# forcefoot.net
KiCad netlist of a schematic drawn in EAGLE
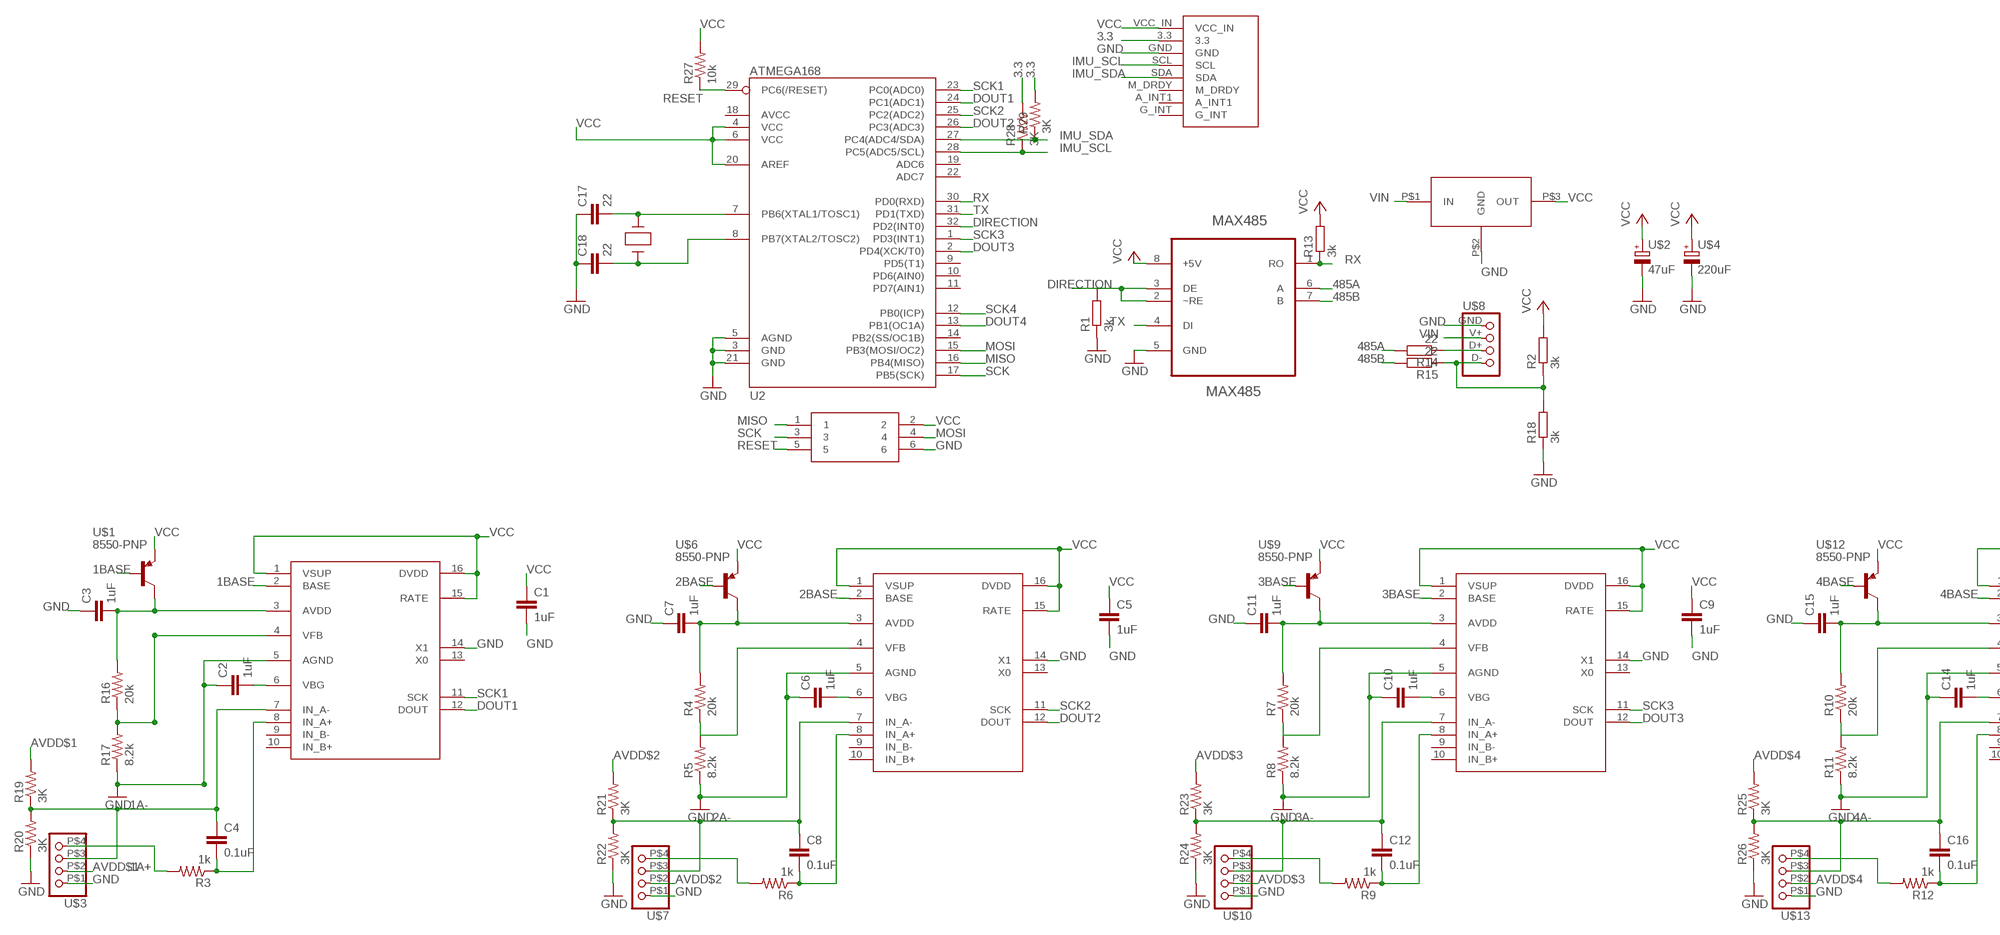
[diagram p0: schematic, sheet 1, part 1 of 2]
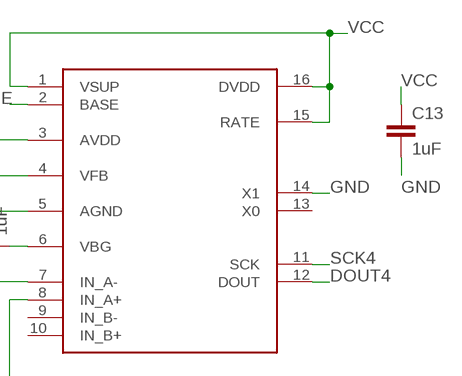
[diagram p1: schematic, sheet 1, part 2 of 2]

(export (version "E")
  (design (tool "Eeschema 10.0.6"))
  (components
    (comp (ref "C1")
      (value "1uF")
      (footprint "eagle-import:0805")
      (libsource (lib "eagle-import") (part "CAP0805"))
    )
    (comp (ref "C2")
      (value "1uF")
      (footprint "eagle-import:0805")
      (libsource (lib "eagle-import") (part "CAP0805"))
    )
    (comp (ref "C3")
      (value "1uF")
      (footprint "eagle-import:0805")
      (libsource (lib "eagle-import") (part "CAP0805"))
    )
    (comp (ref "C4")
      (value "0.1uF")
      (footprint "eagle-import:0805")
      (libsource (lib "eagle-import") (part "CAP0805"))
    )
    (comp (ref "C5")
      (value "1uF")
      (footprint "eagle-import:0805")
      (libsource (lib "eagle-import") (part "CAP0805"))
    )
    (comp (ref "C6")
      (value "1uF")
      (footprint "eagle-import:0805")
      (libsource (lib "eagle-import") (part "CAP0805"))
    )
    (comp (ref "C7")
      (value "1uF")
      (footprint "eagle-import:0805")
      (libsource (lib "eagle-import") (part "CAP0805"))
    )
    (comp (ref "C8")
      (value "0.1uF")
      (footprint "eagle-import:0805")
      (libsource (lib "eagle-import") (part "CAP0805"))
    )
    (comp (ref "C9")
      (value "1uF")
      (footprint "eagle-import:0805")
      (libsource (lib "eagle-import") (part "CAP0805"))
    )
    (comp (ref "C10")
      (value "1uF")
      (footprint "eagle-import:0805")
      (libsource (lib "eagle-import") (part "CAP0805"))
    )
    (comp (ref "C11")
      (value "1uF")
      (footprint "eagle-import:0805")
      (libsource (lib "eagle-import") (part "CAP0805"))
    )
    (comp (ref "C12")
      (value "0.1uF")
      (footprint "eagle-import:0805")
      (libsource (lib "eagle-import") (part "CAP0805"))
    )
    (comp (ref "C13")
      (value "1uF")
      (footprint "eagle-import:0805")
      (libsource (lib "eagle-import") (part "CAP0805"))
    )
    (comp (ref "C14")
      (value "1uF")
      (footprint "eagle-import:0805")
      (libsource (lib "eagle-import") (part "CAP0805"))
    )
    (comp (ref "C15")
      (value "1uF")
      (footprint "eagle-import:0805")
      (libsource (lib "eagle-import") (part "CAP0805"))
    )
    (comp (ref "C16")
      (value "0.1uF")
      (footprint "eagle-import:0805")
      (libsource (lib "eagle-import") (part "CAP0805"))
    )
    (comp (ref "C17")
      (value "22")
      (footprint "eagle-import:C0603")
      (libsource (lib "eagle-import") (part "C_EU_22PF"))
    )
    (comp (ref "C18")
      (value "22")
      (footprint "eagle-import:C0603")
      (libsource (lib "eagle-import") (part "C_EU_22PF"))
    )
    (comp (ref "HX1")
      (value "HX711SO16")
      (footprint "eagle-import:SO16")
      (libsource (lib "eagle-import") (part "HX711SO16"))
    )
    (comp (ref "HX2")
      (value "HX711SO16")
      (footprint "eagle-import:SO16")
      (libsource (lib "eagle-import") (part "HX711SO16"))
    )
    (comp (ref "HX3")
      (value "HX711SO16")
      (footprint "eagle-import:SO16")
      (libsource (lib "eagle-import") (part "HX711SO16"))
    )
    (comp (ref "HX4")
      (value "HX711SO16")
      (footprint "eagle-import:SO16")
      (libsource (lib "eagle-import") (part "HX711SO16"))
    )
    (comp (ref "MAX485")
      (value "MAX485")
      (footprint "eagle-import:SO8")
      (fields (field (name "MPN") "MAX485EESA+"))
      (libsource (lib "eagle-import") (part "MAX485"))
    )
    (comp (ref "R1")
      (value "3k")
      (footprint "eagle-import:R0805")
      (libsource (lib "eagle-import") (part "RESISTANCE-R0805"))
    )
    (comp (ref "R2")
      (value "3k")
      (footprint "eagle-import:R0805")
      (libsource (lib "eagle-import") (part "RESISTANCE-R0805"))
    )
    (comp (ref "R3")
      (value "1k")
      (footprint "eagle-import:0805")
      (libsource (lib "eagle-import") (part "RESISTOR0805-RES"))
    )
    (comp (ref "R4")
      (value "20k")
      (footprint "eagle-import:0805")
      (libsource (lib "eagle-import") (part "RESISTOR0805-RES"))
    )
    (comp (ref "R5")
      (value "8.2k")
      (footprint "eagle-import:0805")
      (libsource (lib "eagle-import") (part "RESISTOR0805-RES"))
    )
    (comp (ref "R6")
      (value "1k")
      (footprint "eagle-import:0805")
      (libsource (lib "eagle-import") (part "RESISTOR0805-RES"))
    )
    (comp (ref "R7")
      (value "20k")
      (footprint "eagle-import:0805")
      (libsource (lib "eagle-import") (part "RESISTOR0805-RES"))
    )
    (comp (ref "R8")
      (value "8.2k")
      (footprint "eagle-import:0805")
      (libsource (lib "eagle-import") (part "RESISTOR0805-RES"))
    )
    (comp (ref "R9")
      (value "1k")
      (footprint "eagle-import:0805")
      (libsource (lib "eagle-import") (part "RESISTOR0805-RES"))
    )
    (comp (ref "R10")
      (value "20k")
      (footprint "eagle-import:0805")
      (libsource (lib "eagle-import") (part "RESISTOR0805-RES"))
    )
    (comp (ref "R11")
      (value "8.2k")
      (footprint "eagle-import:0805")
      (libsource (lib "eagle-import") (part "RESISTOR0805-RES"))
    )
    (comp (ref "R12")
      (value "1k")
      (footprint "eagle-import:0805")
      (libsource (lib "eagle-import") (part "RESISTOR0805-RES"))
    )
    (comp (ref "R13")
      (value "3k")
      (footprint "eagle-import:R0805")
      (libsource (lib "eagle-import") (part "RESISTANCE-R0805"))
    )
    (comp (ref "R14")
      (value "22")
      (footprint "eagle-import:R0805")
      (libsource (lib "eagle-import") (part "RESISTANCE-R0805"))
    )
    (comp (ref "R15")
      (value "22")
      (footprint "eagle-import:R0805")
      (libsource (lib "eagle-import") (part "RESISTANCE-R0805"))
    )
    (comp (ref "R16")
      (value "20k")
      (footprint "eagle-import:0805")
      (libsource (lib "eagle-import") (part "RESISTOR0805-RES"))
    )
    (comp (ref "R17")
      (value "8.2k")
      (footprint "eagle-import:0805")
      (libsource (lib "eagle-import") (part "RESISTOR0805-RES"))
    )
    (comp (ref "R18")
      (value "3k")
      (footprint "eagle-import:R0805")
      (libsource (lib "eagle-import") (part "RESISTANCE-R0805"))
    )
    (comp (ref "R19")
      (value "3K")
      (footprint "eagle-import:0805")
      (libsource (lib "eagle-import") (part "RESISTOR0805-RES"))
    )
    (comp (ref "R20")
      (value "3K")
      (footprint "eagle-import:0805")
      (libsource (lib "eagle-import") (part "RESISTOR0805-RES"))
    )
    (comp (ref "R21")
      (value "3K")
      (footprint "eagle-import:0805")
      (libsource (lib "eagle-import") (part "RESISTOR0805-RES"))
    )
    (comp (ref "R22")
      (value "3K")
      (footprint "eagle-import:0805")
      (libsource (lib "eagle-import") (part "RESISTOR0805-RES"))
    )
    (comp (ref "R23")
      (value "3K")
      (footprint "eagle-import:0805")
      (libsource (lib "eagle-import") (part "RESISTOR0805-RES"))
    )
    (comp (ref "R24")
      (value "3K")
      (footprint "eagle-import:0805")
      (libsource (lib "eagle-import") (part "RESISTOR0805-RES"))
    )
    (comp (ref "R25")
      (value "3K")
      (footprint "eagle-import:0805")
      (libsource (lib "eagle-import") (part "RESISTOR0805-RES"))
    )
    (comp (ref "R26")
      (value "3K")
      (footprint "eagle-import:0805")
      (libsource (lib "eagle-import") (part "RESISTOR0805-RES"))
    )
    (comp (ref "R27")
      (value "10k")
      (footprint "eagle-import:0805")
      (libsource (lib "eagle-import") (part "RESISTOR0805-RES"))
    )
    (comp (ref "R28")
      (value "3K")
      (footprint "eagle-import:0805")
      (libsource (lib "eagle-import") (part "RESISTOR0805-RES"))
    )
    (comp (ref "R29")
      (value "3K")
      (footprint "eagle-import:0805")
      (libsource (lib "eagle-import") (part "RESISTOR0805-RES"))
    )
    (comp (ref "U$1")
      (value "8550-PNP")
      (footprint "eagle-import:SOT-23")
      (libsource (lib "eagle-import") (part "8550-PNP"))
    )
    (comp (ref "U$2")
      (value "47uF")
      (footprint "eagle-import:PANASONIC_D")
      (libsource (lib "eagle-import") (part "CPOL_EUPANASONIC_D"))
    )
    (comp (ref "U$3")
      (value "CONNEC_1X041.5")
      (footprint "eagle-import:4P1.5")
      (libsource (lib "eagle-import") (part "CONNEC_1X041.5"))
    )
    (comp (ref "U$4")
      (value "220uF")
      (footprint "eagle-import:PANASONIC_D8")
      (libsource (lib "eagle-import") (part "CPOL_EUPANASONIC_D8"))
    )
    (comp (ref "U$5")
      (value "REG_5V")
      (footprint "eagle-import:TRACOPOWER")
      (libsource (lib "eagle-import") (part "REG_5V"))
    )
    (comp (ref "U$6")
      (value "8550-PNP")
      (footprint "eagle-import:SOT-23")
      (libsource (lib "eagle-import") (part "8550-PNP"))
    )
    (comp (ref "U$7")
      (value "CONNEC_1X041.5")
      (footprint "eagle-import:4P1.5")
      (libsource (lib "eagle-import") (part "CONNEC_1X041.5"))
    )
    (comp (ref "U$8")
      (value "CONNEC_1X04_485")
      (footprint "eagle-import:CONNEC_485")
      (libsource (lib "eagle-import") (part "CONNEC_1X04_485"))
    )
    (comp (ref "U$9")
      (value "8550-PNP")
      (footprint "eagle-import:SOT-23")
      (libsource (lib "eagle-import") (part "8550-PNP"))
    )
    (comp (ref "U$10")
      (value "CONNEC_1X041.5")
      (footprint "eagle-import:4P1.5")
      (libsource (lib "eagle-import") (part "CONNEC_1X041.5"))
    )
    (comp (ref "U$12")
      (value "8550-PNP")
      (footprint "eagle-import:SOT-23")
      (libsource (lib "eagle-import") (part "8550-PNP"))
    )
    (comp (ref "U$13")
      (value "CONNEC_1X041.5")
      (footprint "eagle-import:4P1.5")
      (libsource (lib "eagle-import") (part "CONNEC_1X041.5"))
    )
    (comp (ref "U$17")
      (value "GY-85")
      (footprint "eagle-import:GY-85")
      (libsource (lib "eagle-import") (part "GY-85"))
    )
    (comp (ref "U$28")
      (value "CONNEC_2X03")
      (footprint "eagle-import:CONNEC_2X03")
      (libsource (lib "eagle-import") (part "CONNEC_2X03"))
    )
    (comp (ref "U2")
      (value "ATMEGA168")
      (footprint "eagle-import:TQFP32-08")
      (libsource (lib "eagle-import") (part "ATMEGA168"))
    )
    (comp (ref "XTAL1")
      (value "QUARTZ")
      (footprint "eagle-import:HC49US")
      (libsource (lib "eagle-import") (part "QUARTZ"))
    )
  )
  (nets
    (net (code "1") (name "/1A+") (class "Default")
      (node (ref "R3") (pin "2") (pinfunction "2_2") (pintype "passive"))
      (node (ref "U$3") (pin "P$4") (pinfunction "4_P$4") (pintype "passive"))
    )
    (net (code "2") (name "/1A-") (class "Default")
      (node (ref "C4") (pin "1") (pinfunction "1_1") (pintype "passive"))
      (node (ref "HX1") (pin "7") (pinfunction "IN_A-_7") (pintype "bidirectional"))
      (node (ref "R19") (pin "1") (pinfunction "1_1") (pintype "passive"))
      (node (ref "R20") (pin "2") (pinfunction "2_2") (pintype "passive"))
      (node (ref "U$3") (pin "P$3") (pinfunction "3_P$3") (pintype "passive"))
    )
    (net (code "3") (name "/1BASE") (class "Default")
      (node (ref "HX1") (pin "2") (pinfunction "BASE_2") (pintype "bidirectional"))
      (node (ref "U$1") (pin "1") (pinfunction "B_1") (pintype "passive"))
    )
    (net (code "4") (name "/2A-") (class "Default")
      (node (ref "C8") (pin "1") (pinfunction "1_1") (pintype "passive"))
      (node (ref "HX2") (pin "7") (pinfunction "IN_A-_7") (pintype "bidirectional"))
      (node (ref "R21") (pin "1") (pinfunction "1_1") (pintype "passive"))
      (node (ref "R22") (pin "2") (pinfunction "2_2") (pintype "passive"))
      (node (ref "U$7") (pin "P$3") (pinfunction "3_P$3") (pintype "passive"))
    )
    (net (code "5") (name "/2BASE") (class "Default")
      (node (ref "HX2") (pin "2") (pinfunction "BASE_2") (pintype "bidirectional"))
      (node (ref "U$6") (pin "1") (pinfunction "B_1") (pintype "passive"))
    )
    (net (code "6") (name "/3.3") (class "Default")
      (node (ref "R28") (pin "2") (pinfunction "2_2") (pintype "passive"))
      (node (ref "R29") (pin "2") (pinfunction "2_2") (pintype "passive"))
      (node (ref "U$17") (pin "3.3") (pinfunction "3.3_3.3") (pintype "bidirectional"))
    )
    (net (code "7") (name "/3A-") (class "Default")
      (node (ref "C12") (pin "1") (pinfunction "1_1") (pintype "passive"))
      (node (ref "HX3") (pin "7") (pinfunction "IN_A-_7") (pintype "bidirectional"))
      (node (ref "R23") (pin "1") (pinfunction "1_1") (pintype "passive"))
      (node (ref "R24") (pin "2") (pinfunction "2_2") (pintype "passive"))
      (node (ref "U$10") (pin "P$3") (pinfunction "3_P$3") (pintype "passive"))
    )
    (net (code "8") (name "/3BASE") (class "Default")
      (node (ref "HX3") (pin "2") (pinfunction "BASE_2") (pintype "bidirectional"))
      (node (ref "U$9") (pin "1") (pinfunction "B_1") (pintype "passive"))
    )
    (net (code "9") (name "/4A-") (class "Default")
      (node (ref "C16") (pin "1") (pinfunction "1_1") (pintype "passive"))
      (node (ref "HX4") (pin "7") (pinfunction "IN_A-_7") (pintype "bidirectional"))
      (node (ref "R25") (pin "1") (pinfunction "1_1") (pintype "passive"))
      (node (ref "R26") (pin "2") (pinfunction "2_2") (pintype "passive"))
      (node (ref "U$13") (pin "P$3") (pinfunction "3_P$3") (pintype "passive"))
    )
    (net (code "10") (name "/4BASE") (class "Default")
      (node (ref "HX4") (pin "2") (pinfunction "BASE_2") (pintype "bidirectional"))
      (node (ref "U$12") (pin "1") (pinfunction "B_1") (pintype "passive"))
    )
    (net (code "11") (name "/485A") (class "Default")
      (node (ref "MAX485") (pin "6") (pinfunction "A_6") (pintype "bidirectional"))
      (node (ref "R14") (pin "2") (pinfunction "2_2") (pintype "passive"))
    )
    (net (code "12") (name "/485B") (class "Default")
      (node (ref "MAX485") (pin "7") (pinfunction "B_7") (pintype "bidirectional"))
      (node (ref "R15") (pin "2") (pinfunction "2_2") (pintype "passive"))
    )
    (net (code "13") (name "/AVDD$1") (class "Default")
      (node (ref "C3") (pin "2") (pinfunction "2_2") (pintype "passive"))
      (node (ref "HX1") (pin "3") (pinfunction "AVDD_3") (pintype "bidirectional"))
      (node (ref "R16") (pin "2") (pinfunction "2_2") (pintype "passive"))
      (node (ref "R19") (pin "2") (pinfunction "2_2") (pintype "passive"))
      (node (ref "U$1") (pin "3") (pinfunction "C_3") (pintype "passive"))
      (node (ref "U$3") (pin "P$2") (pinfunction "2_P$2") (pintype "passive"))
    )
    (net (code "14") (name "/AVDD$2") (class "Default")
      (node (ref "C7") (pin "2") (pinfunction "2_2") (pintype "passive"))
      (node (ref "HX2") (pin "3") (pinfunction "AVDD_3") (pintype "bidirectional"))
      (node (ref "R21") (pin "2") (pinfunction "2_2") (pintype "passive"))
      (node (ref "R4") (pin "2") (pinfunction "2_2") (pintype "passive"))
      (node (ref "U$6") (pin "3") (pinfunction "C_3") (pintype "passive"))
      (node (ref "U$7") (pin "P$2") (pinfunction "2_P$2") (pintype "passive"))
    )
    (net (code "15") (name "/AVDD$3") (class "Default")
      (node (ref "C11") (pin "2") (pinfunction "2_2") (pintype "passive"))
      (node (ref "HX3") (pin "3") (pinfunction "AVDD_3") (pintype "bidirectional"))
      (node (ref "R23") (pin "2") (pinfunction "2_2") (pintype "passive"))
      (node (ref "R7") (pin "2") (pinfunction "2_2") (pintype "passive"))
      (node (ref "U$10") (pin "P$2") (pinfunction "2_P$2") (pintype "passive"))
      (node (ref "U$9") (pin "3") (pinfunction "C_3") (pintype "passive"))
    )
    (net (code "16") (name "/AVDD$4") (class "Default")
      (node (ref "C15") (pin "2") (pinfunction "2_2") (pintype "passive"))
      (node (ref "HX4") (pin "3") (pinfunction "AVDD_3") (pintype "bidirectional"))
      (node (ref "R10") (pin "2") (pinfunction "2_2") (pintype "passive"))
      (node (ref "R25") (pin "2") (pinfunction "2_2") (pintype "passive"))
      (node (ref "U$12") (pin "3") (pinfunction "C_3") (pintype "passive"))
      (node (ref "U$13") (pin "P$2") (pinfunction "2_P$2") (pintype "passive"))
    )
    (net (code "17") (name "/DIRECTION") (class "Default")
      (node (ref "MAX485") (pin "2") (pinfunction "~{RE}_2") (pintype "input"))
      (node (ref "MAX485") (pin "3") (pinfunction "DE_3") (pintype "input"))
      (node (ref "R1") (pin "2") (pinfunction "2_2") (pintype "passive"))
      (node (ref "U2") (pin "32") (pinfunction "PD2(INT0)_32") (pintype "bidirectional"))
    )
    (net (code "18") (name "/DOUT1") (class "Default")
      (node (ref "HX1") (pin "12") (pinfunction "DOUT_12") (pintype "bidirectional"))
      (node (ref "U2") (pin "24") (pinfunction "PC1(ADC1)_24") (pintype "bidirectional"))
    )
    (net (code "19") (name "/DOUT2") (class "Default")
      (node (ref "HX2") (pin "12") (pinfunction "DOUT_12") (pintype "bidirectional"))
      (node (ref "U2") (pin "26") (pinfunction "PC3(ADC3)_26") (pintype "bidirectional"))
    )
    (net (code "20") (name "/DOUT3") (class "Default")
      (node (ref "HX3") (pin "12") (pinfunction "DOUT_12") (pintype "bidirectional"))
      (node (ref "U2") (pin "2") (pinfunction "PD4(XCK/T0)_2") (pintype "bidirectional"))
    )
    (net (code "21") (name "/DOUT4") (class "Default")
      (node (ref "HX4") (pin "12") (pinfunction "DOUT_12") (pintype "bidirectional"))
      (node (ref "U2") (pin "13") (pinfunction "PB1(OC1A)_13") (pintype "bidirectional"))
    )
    (net (code "22") (name "/IMU_SCL") (class "Default")
      (node (ref "R28") (pin "1") (pinfunction "1_1") (pintype "passive"))
      (node (ref "U$17") (pin "SCL") (pinfunction "SCL_SCL") (pintype "bidirectional"))
      (node (ref "U2") (pin "28") (pinfunction "PC5(ADC5/SCL)_28") (pintype "bidirectional"))
    )
    (net (code "23") (name "/IMU_SDA") (class "Default")
      (node (ref "R29") (pin "1") (pinfunction "1_1") (pintype "passive"))
      (node (ref "U$17") (pin "SDA") (pinfunction "SDA_SDA") (pintype "bidirectional"))
      (node (ref "U2") (pin "27") (pinfunction "PC4(ADC4/SDA)_27") (pintype "bidirectional"))
    )
    (net (code "24") (name "/MISO") (class "Default")
      (node (ref "U$28") (pin "1") (pinfunction "1_1") (pintype "bidirectional"))
      (node (ref "U2") (pin "16") (pinfunction "PB4(MISO)_16") (pintype "bidirectional"))
    )
    (net (code "25") (name "/MOSI") (class "Default")
      (node (ref "U$28") (pin "4") (pinfunction "4_4") (pintype "bidirectional"))
      (node (ref "U2") (pin "15") (pinfunction "PB3(MOSI/OC2)_15") (pintype "bidirectional"))
    )
    (net (code "26") (name "/RESET") (class "Default")
      (node (ref "R27") (pin "1") (pinfunction "1_1") (pintype "passive"))
      (node (ref "U$28") (pin "5") (pinfunction "5_5") (pintype "bidirectional"))
      (node (ref "U2") (pin "29") (pinfunction "PC6(/RESET)_29") (pintype "bidirectional"))
    )
    (net (code "27") (name "/RX") (class "Default")
      (node (ref "MAX485") (pin "1") (pinfunction "RO_1") (pintype "output"))
      (node (ref "R13") (pin "1") (pinfunction "1_1") (pintype "passive"))
      (node (ref "U2") (pin "30") (pinfunction "PD0(RXD)_30") (pintype "bidirectional"))
    )
    (net (code "28") (name "/SCK") (class "Default")
      (node (ref "U$28") (pin "3") (pinfunction "3_3") (pintype "bidirectional"))
      (node (ref "U2") (pin "17") (pinfunction "PB5(SCK)_17") (pintype "bidirectional"))
    )
    (net (code "29") (name "/SCK1") (class "Default")
      (node (ref "HX1") (pin "11") (pinfunction "SCK_11") (pintype "bidirectional"))
      (node (ref "U2") (pin "23") (pinfunction "PC0(ADC0)_23") (pintype "bidirectional"))
    )
    (net (code "30") (name "/SCK2") (class "Default")
      (node (ref "HX2") (pin "11") (pinfunction "SCK_11") (pintype "bidirectional"))
      (node (ref "U2") (pin "25") (pinfunction "PC2(ADC2)_25") (pintype "bidirectional"))
    )
    (net (code "31") (name "/SCK3") (class "Default")
      (node (ref "HX3") (pin "11") (pinfunction "SCK_11") (pintype "bidirectional"))
      (node (ref "U2") (pin "1") (pinfunction "PD3(INT1)_1") (pintype "bidirectional"))
    )
    (net (code "32") (name "/SCK4") (class "Default")
      (node (ref "HX4") (pin "11") (pinfunction "SCK_11") (pintype "bidirectional"))
      (node (ref "U2") (pin "12") (pinfunction "PB0(ICP)_12") (pintype "bidirectional"))
    )
    (net (code "33") (name "/TX") (class "Default")
      (node (ref "MAX485") (pin "4") (pinfunction "DI_4") (pintype "input"))
      (node (ref "U2") (pin "31") (pinfunction "PD1(TXD)_31") (pintype "bidirectional"))
    )
    (net (code "34") (name "/VIN") (class "Default")
      (node (ref "U$5") (pin "P$1") (pinfunction "IN_P$1") (pintype "bidirectional"))
      (node (ref "U$8") (pin "V+") (pinfunction "2_V+") (pintype "passive"))
    )
    (net (code "35") (name "GND") (class "Default")
      (node (ref "C1") (pin "2") (pinfunction "2_2") (pintype "passive"))
      (node (ref "C10") (pin "1") (pinfunction "1_1") (pintype "passive"))
      (node (ref "C11") (pin "1") (pinfunction "1_1") (pintype "passive"))
      (node (ref "C13") (pin "2") (pinfunction "2_2") (pintype "passive"))
      (node (ref "C14") (pin "1") (pinfunction "1_1") (pintype "passive"))
      (node (ref "C15") (pin "1") (pinfunction "1_1") (pintype "passive"))
      (node (ref "C17") (pin "1") (pinfunction "1_1") (pintype "passive"))
      (node (ref "C18") (pin "1") (pinfunction "1_1") (pintype "passive"))
      (node (ref "C2") (pin "1") (pinfunction "1_1") (pintype "passive"))
      (node (ref "C3") (pin "1") (pinfunction "1_1") (pintype "passive"))
      (node (ref "C5") (pin "2") (pinfunction "2_2") (pintype "passive"))
      (node (ref "C6") (pin "1") (pinfunction "1_1") (pintype "passive"))
      (node (ref "C7") (pin "1") (pinfunction "1_1") (pintype "passive"))
      (node (ref "C9") (pin "2") (pinfunction "2_2") (pintype "passive"))
      (node (ref "HX1") (pin "14") (pinfunction "X1_14") (pintype "bidirectional"))
      (node (ref "HX1") (pin "5") (pinfunction "AGND_5") (pintype "bidirectional"))
      (node (ref "HX2") (pin "14") (pinfunction "X1_14") (pintype "bidirectional"))
      (node (ref "HX2") (pin "5") (pinfunction "AGND_5") (pintype "bidirectional"))
      (node (ref "HX3") (pin "14") (pinfunction "X1_14") (pintype "bidirectional"))
      (node (ref "HX3") (pin "5") (pinfunction "AGND_5") (pintype "bidirectional"))
      (node (ref "HX4") (pin "14") (pinfunction "X1_14") (pintype "bidirectional"))
      (node (ref "HX4") (pin "5") (pinfunction "AGND_5") (pintype "bidirectional"))
      (node (ref "MAX485") (pin "5") (pinfunction "GND_5") (pintype "passive"))
      (node (ref "R1") (pin "1") (pinfunction "1_1") (pintype "passive"))
      (node (ref "R11") (pin "1") (pinfunction "1_1") (pintype "passive"))
      (node (ref "R17") (pin "1") (pinfunction "1_1") (pintype "passive"))
      (node (ref "R18") (pin "1") (pinfunction "1_1") (pintype "passive"))
      (node (ref "R20") (pin "1") (pinfunction "1_1") (pintype "passive"))
      (node (ref "R22") (pin "1") (pinfunction "1_1") (pintype "passive"))
      (node (ref "R24") (pin "1") (pinfunction "1_1") (pintype "passive"))
      (node (ref "R26") (pin "1") (pinfunction "1_1") (pintype "passive"))
      (node (ref "R5") (pin "1") (pinfunction "1_1") (pintype "passive"))
      (node (ref "R8") (pin "1") (pinfunction "1_1") (pintype "passive"))
      (node (ref "U$10") (pin "P$1") (pinfunction "1_P$1") (pintype "passive"))
      (node (ref "U$13") (pin "P$1") (pinfunction "1_P$1") (pintype "passive"))
      (node (ref "U$17") (pin "GND") (pinfunction "GND_GND") (pintype "bidirectional"))
      (node (ref "U$2") (pin "-") (pinfunction "-_-") (pintype "passive"))
      (node (ref "U$28") (pin "6") (pinfunction "6_6") (pintype "bidirectional"))
      (node (ref "U$3") (pin "P$1") (pinfunction "1_P$1") (pintype "passive"))
      (node (ref "U$4") (pin "-") (pinfunction "-_-") (pintype "passive"))
      (node (ref "U$5") (pin "P$2") (pinfunction "GND_P$2") (pintype "bidirectional"))
      (node (ref "U$7") (pin "P$1") (pinfunction "1_P$1") (pintype "passive"))
      (node (ref "U$8") (pin "GND") (pinfunction "1_GND") (pintype "passive"))
      (node (ref "U2") (pin "21") (pinfunction "GND_21") (pintype "bidirectional"))
      (node (ref "U2") (pin "3") (pinfunction "GND_3") (pintype "bidirectional"))
      (node (ref "U2") (pin "5") (pinfunction "AGND_5") (pintype "bidirectional"))
    )
    (net (code "36") (name "Net-(HX1-IN_A+)") (class "Default")
      (node (ref "C4") (pin "2") (pinfunction "2_2") (pintype "passive"))
      (node (ref "HX1") (pin "8") (pinfunction "IN_A+_8") (pintype "bidirectional"))
      (node (ref "R3") (pin "1") (pinfunction "1_1") (pintype "passive"))
    )
    (net (code "37") (name "Net-(HX1-VBG)") (class "Default")
      (node (ref "C2") (pin "2") (pinfunction "2_2") (pintype "passive"))
      (node (ref "HX1") (pin "6") (pinfunction "VBG_6") (pintype "bidirectional"))
    )
    (net (code "38") (name "Net-(HX1-VFB)") (class "Default")
      (node (ref "HX1") (pin "4") (pinfunction "VFB_4") (pintype "bidirectional"))
      (node (ref "R16") (pin "1") (pinfunction "1_1") (pintype "passive"))
      (node (ref "R17") (pin "2") (pinfunction "2_2") (pintype "passive"))
    )
    (net (code "39") (name "Net-(HX2-IN_A+)") (class "Default")
      (node (ref "C8") (pin "2") (pinfunction "2_2") (pintype "passive"))
      (node (ref "HX2") (pin "8") (pinfunction "IN_A+_8") (pintype "bidirectional"))
      (node (ref "R6") (pin "1") (pinfunction "1_1") (pintype "passive"))
    )
    (net (code "40") (name "Net-(HX2-VBG)") (class "Default")
      (node (ref "C6") (pin "2") (pinfunction "2_2") (pintype "passive"))
      (node (ref "HX2") (pin "6") (pinfunction "VBG_6") (pintype "bidirectional"))
    )
    (net (code "41") (name "Net-(HX2-VFB)") (class "Default")
      (node (ref "HX2") (pin "4") (pinfunction "VFB_4") (pintype "bidirectional"))
      (node (ref "R4") (pin "1") (pinfunction "1_1") (pintype "passive"))
      (node (ref "R5") (pin "2") (pinfunction "2_2") (pintype "passive"))
    )
    (net (code "42") (name "Net-(HX3-IN_A+)") (class "Default")
      (node (ref "C12") (pin "2") (pinfunction "2_2") (pintype "passive"))
      (node (ref "HX3") (pin "8") (pinfunction "IN_A+_8") (pintype "bidirectional"))
      (node (ref "R9") (pin "1") (pinfunction "1_1") (pintype "passive"))
    )
    (net (code "43") (name "Net-(HX3-VBG)") (class "Default")
      (node (ref "C10") (pin "2") (pinfunction "2_2") (pintype "passive"))
      (node (ref "HX3") (pin "6") (pinfunction "VBG_6") (pintype "bidirectional"))
    )
    (net (code "44") (name "Net-(HX3-VFB)") (class "Default")
      (node (ref "HX3") (pin "4") (pinfunction "VFB_4") (pintype "bidirectional"))
      (node (ref "R7") (pin "1") (pinfunction "1_1") (pintype "passive"))
      (node (ref "R8") (pin "2") (pinfunction "2_2") (pintype "passive"))
    )
    (net (code "45") (name "Net-(HX4-IN_A+)") (class "Default")
      (node (ref "C16") (pin "2") (pinfunction "2_2") (pintype "passive"))
      (node (ref "HX4") (pin "8") (pinfunction "IN_A+_8") (pintype "bidirectional"))
      (node (ref "R12") (pin "1") (pinfunction "1_1") (pintype "passive"))
    )
    (net (code "46") (name "Net-(HX4-VBG)") (class "Default")
      (node (ref "C14") (pin "2") (pinfunction "2_2") (pintype "passive"))
      (node (ref "HX4") (pin "6") (pinfunction "VBG_6") (pintype "bidirectional"))
    )
    (net (code "47") (name "Net-(HX4-VFB)") (class "Default")
      (node (ref "HX4") (pin "4") (pinfunction "VFB_4") (pintype "bidirectional"))
      (node (ref "R10") (pin "1") (pinfunction "1_1") (pintype "passive"))
      (node (ref "R11") (pin "2") (pinfunction "2_2") (pintype "passive"))
    )
    (net (code "48") (name "Net-(U$7-4)") (class "Default")
      (node (ref "R6") (pin "2") (pinfunction "2_2") (pintype "passive"))
      (node (ref "U$7") (pin "P$4") (pinfunction "4_P$4") (pintype "passive"))
    )
    (net (code "49") (name "Net-(U$8-3)") (class "Default")
      (node (ref "R14") (pin "1") (pinfunction "1_1") (pintype "passive"))
      (node (ref "U$8") (pin "D+") (pinfunction "3_D+") (pintype "passive"))
    )
    (net (code "50") (name "Net-(U$8-4)") (class "Default")
      (node (ref "R15") (pin "1") (pinfunction "1_1") (pintype "passive"))
      (node (ref "R18") (pin "2") (pinfunction "2_2") (pintype "passive"))
      (node (ref "R2") (pin "1") (pinfunction "1_1") (pintype "passive"))
      (node (ref "U$8") (pin "D-") (pinfunction "4_D-") (pintype "passive"))
    )
    (net (code "51") (name "Net-(U$10-4)") (class "Default")
      (node (ref "R9") (pin "2") (pinfunction "2_2") (pintype "passive"))
      (node (ref "U$10") (pin "P$4") (pinfunction "4_P$4") (pintype "passive"))
    )
    (net (code "52") (name "Net-(U$13-4)") (class "Default")
      (node (ref "R12") (pin "2") (pinfunction "2_2") (pintype "passive"))
      (node (ref "U$13") (pin "P$4") (pinfunction "4_P$4") (pintype "passive"))
    )
    (net (code "53") (name "Net-(U2-PB6(XTAL1{slash}TOSC1))") (class "Default")
      (node (ref "C17") (pin "2") (pinfunction "2_2") (pintype "passive"))
      (node (ref "U2") (pin "7") (pinfunction "PB6(XTAL1/TOSC1)_7") (pintype "bidirectional"))
      (node (ref "XTAL1") (pin "2") (pinfunction "2_2") (pintype "bidirectional"))
    )
    (net (code "54") (name "Net-(U2-PB7(XTAL2{slash}TOSC2))") (class "Default")
      (node (ref "C18") (pin "2") (pinfunction "2_2") (pintype "passive"))
      (node (ref "U2") (pin "8") (pinfunction "PB7(XTAL2/TOSC2)_8") (pintype "bidirectional"))
      (node (ref "XTAL1") (pin "1") (pinfunction "1_1") (pintype "bidirectional"))
    )
    (net (code "55") (name "VCC") (class "Default")
      (node (ref "C1") (pin "1") (pinfunction "1_1") (pintype "passive"))
      (node (ref "C13") (pin "1") (pinfunction "1_1") (pintype "passive"))
      (node (ref "C5") (pin "1") (pinfunction "1_1") (pintype "passive"))
      (node (ref "C9") (pin "1") (pinfunction "1_1") (pintype "passive"))
      (node (ref "HX1") (pin "1") (pinfunction "VSUP_1") (pintype "bidirectional"))
      (node (ref "HX1") (pin "15") (pinfunction "RATE_15") (pintype "bidirectional"))
      (node (ref "HX1") (pin "16") (pinfunction "DVDD_16") (pintype "bidirectional"))
      (node (ref "HX2") (pin "1") (pinfunction "VSUP_1") (pintype "bidirectional"))
      (node (ref "HX2") (pin "15") (pinfunction "RATE_15") (pintype "bidirectional"))
      (node (ref "HX2") (pin "16") (pinfunction "DVDD_16") (pintype "bidirectional"))
      (node (ref "HX3") (pin "1") (pinfunction "VSUP_1") (pintype "bidirectional"))
      (node (ref "HX3") (pin "15") (pinfunction "RATE_15") (pintype "bidirectional"))
      (node (ref "HX3") (pin "16") (pinfunction "DVDD_16") (pintype "bidirectional"))
      (node (ref "HX4") (pin "1") (pinfunction "VSUP_1") (pintype "bidirectional"))
      (node (ref "HX4") (pin "15") (pinfunction "RATE_15") (pintype "bidirectional"))
      (node (ref "HX4") (pin "16") (pinfunction "DVDD_16") (pintype "bidirectional"))
      (node (ref "MAX485") (pin "8") (pinfunction "+5V_8") (pintype "power_in"))
      (node (ref "R13") (pin "2") (pinfunction "2_2") (pintype "passive"))
      (node (ref "R2") (pin "2") (pinfunction "2_2") (pintype "passive"))
      (node (ref "R27") (pin "2") (pinfunction "2_2") (pintype "passive"))
      (node (ref "U$1") (pin "2") (pinfunction "E_2") (pintype "passive"))
      (node (ref "U$12") (pin "2") (pinfunction "E_2") (pintype "passive"))
      (node (ref "U$17") (pin "VCC_IN") (pinfunction "VCC_IN_VCC_IN") (pintype "bidirectional"))
      (node (ref "U$2") (pin "+") (pinfunction "+_+") (pintype "passive"))
      (node (ref "U$28") (pin "2") (pinfunction "2_2") (pintype "bidirectional"))
      (node (ref "U$4") (pin "+") (pinfunction "+_+") (pintype "passive"))
      (node (ref "U$5") (pin "P$3") (pinfunction "OUT_P$3") (pintype "bidirectional"))
      (node (ref "U$6") (pin "2") (pinfunction "E_2") (pintype "passive"))
      (node (ref "U$9") (pin "2") (pinfunction "E_2") (pintype "passive"))
      (node (ref "U2") (pin "20") (pinfunction "AREF_20") (pintype "bidirectional"))
      (node (ref "U2") (pin "4") (pinfunction "VCC_4") (pintype "bidirectional"))
      (node (ref "U2") (pin "6") (pinfunction "VCC_6") (pintype "bidirectional"))
    )
    (net (code "56") (name "unconnected-(HX1-IN_B+-Pad10)") (class "Default")
      (node (ref "HX1") (pin "10") (pinfunction "IN_B+_10") (pintype "bidirectional"))
    )
    (net (code "57") (name "unconnected-(HX1-IN_B--Pad9)") (class "Default")
      (node (ref "HX1") (pin "9") (pinfunction "IN_B-_9") (pintype "bidirectional"))
    )
    (net (code "58") (name "unconnected-(HX1-X0-Pad13)") (class "Default")
      (node (ref "HX1") (pin "13") (pinfunction "X0_13") (pintype "bidirectional"))
    )
    (net (code "59") (name "unconnected-(HX2-IN_B+-Pad10)") (class "Default")
      (node (ref "HX2") (pin "10") (pinfunction "IN_B+_10") (pintype "bidirectional"))
    )
    (net (code "60") (name "unconnected-(HX2-IN_B--Pad9)") (class "Default")
      (node (ref "HX2") (pin "9") (pinfunction "IN_B-_9") (pintype "bidirectional"))
    )
    (net (code "61") (name "unconnected-(HX2-X0-Pad13)") (class "Default")
      (node (ref "HX2") (pin "13") (pinfunction "X0_13") (pintype "bidirectional"))
    )
    (net (code "62") (name "unconnected-(HX3-IN_B+-Pad10)") (class "Default")
      (node (ref "HX3") (pin "10") (pinfunction "IN_B+_10") (pintype "bidirectional"))
    )
    (net (code "63") (name "unconnected-(HX3-IN_B--Pad9)") (class "Default")
      (node (ref "HX3") (pin "9") (pinfunction "IN_B-_9") (pintype "bidirectional"))
    )
    (net (code "64") (name "unconnected-(HX3-X0-Pad13)") (class "Default")
      (node (ref "HX3") (pin "13") (pinfunction "X0_13") (pintype "bidirectional"))
    )
    (net (code "65") (name "unconnected-(HX4-IN_B+-Pad10)") (class "Default")
      (node (ref "HX4") (pin "10") (pinfunction "IN_B+_10") (pintype "bidirectional"))
    )
    (net (code "66") (name "unconnected-(HX4-IN_B--Pad9)") (class "Default")
      (node (ref "HX4") (pin "9") (pinfunction "IN_B-_9") (pintype "bidirectional"))
    )
    (net (code "67") (name "unconnected-(HX4-X0-Pad13)") (class "Default")
      (node (ref "HX4") (pin "13") (pinfunction "X0_13") (pintype "bidirectional"))
    )
    (net (code "68") (name "unconnected-(U$17-PadA_INT1)") (class "Default")
      (node (ref "U$17") (pin "A_INT1") (pinfunction "A_INT1_A_INT1") (pintype "bidirectional"))
    )
    (net (code "69") (name "unconnected-(U$17-PadG_INT)") (class "Default")
      (node (ref "U$17") (pin "G_INT") (pinfunction "G_INT_G_INT") (pintype "bidirectional"))
    )
    (net (code "70") (name "unconnected-(U$17-PadM_DRDY)") (class "Default")
      (node (ref "U$17") (pin "M_DRDY") (pinfunction "M_DRDY_M_DRDY") (pintype "bidirectional"))
    )
    (net (code "71") (name "unconnected-(U2-ADC6-Pad19)") (class "Default")
      (node (ref "U2") (pin "19") (pinfunction "ADC6_19") (pintype "bidirectional"))
    )
    (net (code "72") (name "unconnected-(U2-ADC7-Pad22)") (class "Default")
      (node (ref "U2") (pin "22") (pinfunction "ADC7_22") (pintype "bidirectional"))
    )
    (net (code "73") (name "unconnected-(U2-AVCC-Pad18)") (class "Default")
      (node (ref "U2") (pin "18") (pinfunction "AVCC_18") (pintype "bidirectional"))
    )
    (net (code "74") (name "unconnected-(U2-PB2(SS{slash}OC1B)-Pad14)") (class "Default")
      (node (ref "U2") (pin "14") (pinfunction "PB2(SS/OC1B)_14") (pintype "bidirectional"))
    )
    (net (code "75") (name "unconnected-(U2-PD5(T1)-Pad9)") (class "Default")
      (node (ref "U2") (pin "9") (pinfunction "PD5(T1)_9") (pintype "bidirectional"))
    )
    (net (code "76") (name "unconnected-(U2-PD6(AIN0)-Pad10)") (class "Default")
      (node (ref "U2") (pin "10") (pinfunction "PD6(AIN0)_10") (pintype "bidirectional"))
    )
    (net (code "77") (name "unconnected-(U2-PD7(AIN1)-Pad11)") (class "Default")
      (node (ref "U2") (pin "11") (pinfunction "PD7(AIN1)_11") (pintype "bidirectional"))
    )
  )
)
